# E-21_Neopixel_Blaster.net
KiCad netlist of a schematic drawn in Altium Designer
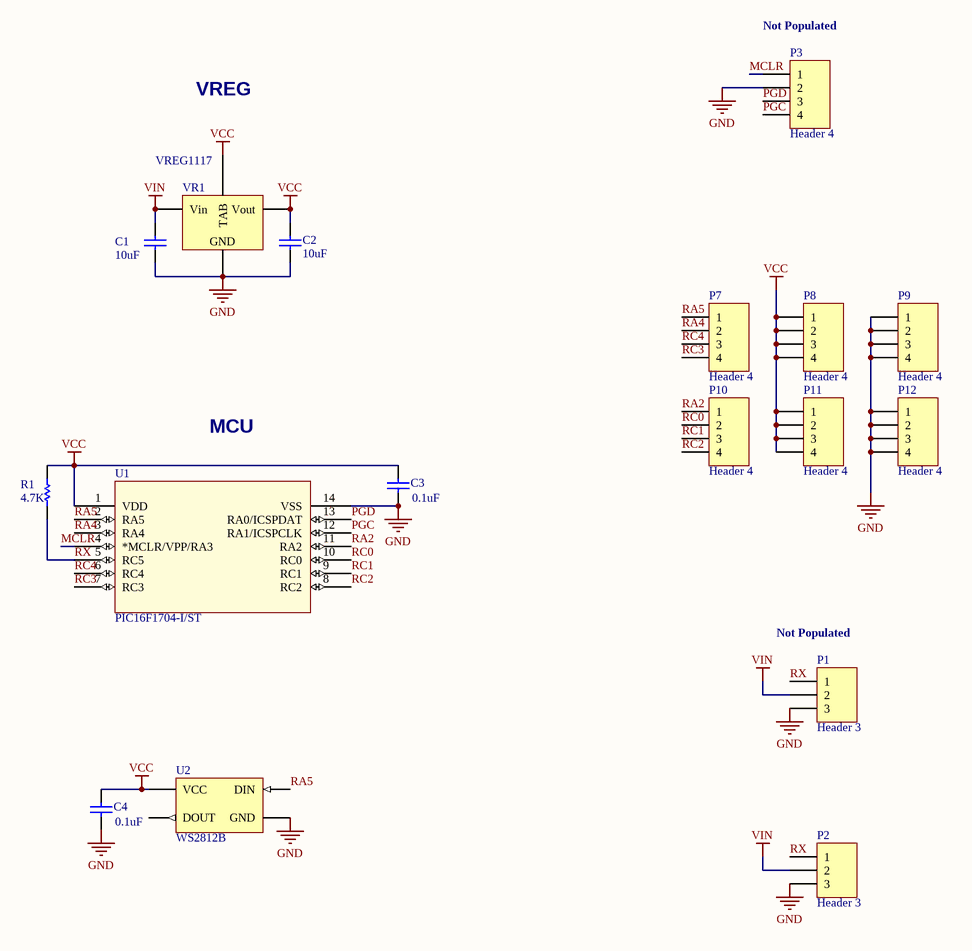
[diagram p0: E-21 Neopixel Blaster.SchDoc]

(export (version "E")
  (design (tool "Eeschema 10.0.6"))
  (components
    (comp (ref "C1")
      (value "10uF")
      (footprint "0805")
      (description "Capacitor")
      (fields (field (name "Comment") "Cap") (field (name "PUBLISHER") "Altium Limited"))
      (libsource (lib "SB_Discrete") (part "Cap"))
    )
    (comp (ref "C2")
      (value "10uF")
      (footprint "0805")
      (description "Capacitor")
      (fields (field (name "Comment") "Cap") (field (name "PUBLISHER") "Altium Limited"))
      (libsource (lib "SB_Discrete") (part "Cap"))
    )
    (comp (ref "C3")
      (value "0.1uF")
      (footprint "0805 TIGHT")
      (description "Capacitor")
      (fields (field (name "Comment") "18pF") (field (name "PUBLISHER") "Altium Limited"))
      (libsource (lib "SB_Discrete") (part "Cap"))
    )
    (comp (ref "C4")
      (value "0.1uF")
      (footprint "0805 TIGHT")
      (description "Capacitor")
      (fields (field (name "Comment") "18pF") (field (name "PUBLISHER") "Altium Limited"))
      (libsource (lib "SB_Discrete") (part "Cap"))
    )
    (comp (ref "P1")
      (value "Header 3")
      (footprint "HDR1X3")
      (description "Header, 3-Pin")
      (fields (field (name "PUBLISHER") "Altium Limited"))
      (libsource (lib "Miscellaneous Connectors") (part "Header 3"))
    )
    (comp (ref "P2")
      (value "Header 3")
      (footprint "JST-PH 3-PIN")
      (description "Header, 3-Pin")
      (fields (field (name "PUBLISHER") "Altium Limited"))
      (libsource (lib "Miscellaneous Connectors") (part "Header 3"))
    )
    (comp (ref "P3")
      (value "Header 4")
      (footprint "MINI PROG4")
      (description "Header, 4-Pin")
      (fields (field (name "PUBLISHER") "Altium Limited"))
      (libsource (lib "Miscellaneous Connectors") (part "Header 4"))
    )
    (comp (ref "P7")
      (value "Header 4")
      (footprint "HDR1X4")
      (description "Header, 4-Pin")
      (fields (field (name "PUBLISHER") "Altium Limited"))
      (libsource (lib "Miscellaneous Connectors") (part "Header 4"))
    )
    (comp (ref "P8")
      (value "Header 4")
      (footprint "HDR1X4")
      (description "Header, 4-Pin")
      (fields (field (name "PUBLISHER") "Altium Limited"))
      (libsource (lib "Miscellaneous Connectors") (part "Header 4"))
    )
    (comp (ref "P9")
      (value "Header 4")
      (footprint "HDR1X4")
      (description "Header, 4-Pin")
      (fields (field (name "PUBLISHER") "Altium Limited"))
      (libsource (lib "Miscellaneous Connectors") (part "Header 4"))
    )
    (comp (ref "P10")
      (value "Header 4")
      (footprint "HDR1X4")
      (description "Header, 4-Pin")
      (fields (field (name "PUBLISHER") "Altium Limited"))
      (libsource (lib "Miscellaneous Connectors") (part "Header 4"))
    )
    (comp (ref "P11")
      (value "Header 4")
      (footprint "HDR1X4")
      (description "Header, 4-Pin")
      (fields (field (name "PUBLISHER") "Altium Limited"))
      (libsource (lib "Miscellaneous Connectors") (part "Header 4"))
    )
    (comp (ref "P12")
      (value "Header 4")
      (footprint "HDR1X4")
      (description "Header, 4-Pin")
      (fields (field (name "PUBLISHER") "Altium Limited"))
      (libsource (lib "Miscellaneous Connectors") (part "Header 4"))
    )
    (comp (ref "R1")
      (value "4.7K")
      (footprint "0805 TIGHT")
      (description "Resistor")
      (fields (field (name "Comment") "Res1") (field (name "PUBLISHER") "Altium Limited"))
      (libsource (lib "SB_Discrete") (part "Res1"))
    )
    (comp (ref "U1")
      (value "PIC16F1704-I/ST")
      (footprint "TSSOP14")
      (libsource (lib "SB_Engineered_Components") (part "PIC16F1503"))
    )
    (comp (ref "U2")
      (value "WS2812B")
      (footprint "ws2812b")
      (libsource (lib "SB_Engineered_Components") (part "WS2812B"))
    )
    (comp (ref "VR1")
      (value "VREG1117")
      (footprint "VREG1117")
      (libsource (lib "SB_Engineered_Components") (part "VREG1117"))
    )
  )
  (nets
    (net (code "1") (name "/MCLR") (class "Default")
      (node (ref "P3") (pin "1") (pinfunction "1_1") (pintype "passive"))
      (node (ref "U1") (pin "4") (pinfunction "*MCLR/VPP/RA3_4") (pintype "bidirectional"))
    )
    (net (code "2") (name "/PGC") (class "Default")
      (node (ref "P3") (pin "4") (pinfunction "4_4") (pintype "passive"))
      (node (ref "U1") (pin "12") (pinfunction "RA1/ICSPCLK_12") (pintype "bidirectional"))
    )
    (net (code "3") (name "/PGD") (class "Default")
      (node (ref "P3") (pin "3") (pinfunction "3_3") (pintype "passive"))
      (node (ref "U1") (pin "13") (pinfunction "RA0/ICSPDAT_13") (pintype "bidirectional"))
    )
    (net (code "4") (name "/RA2") (class "Default")
      (node (ref "P10") (pin "1") (pinfunction "1_1") (pintype "passive"))
      (node (ref "U1") (pin "11") (pinfunction "RA2_11") (pintype "bidirectional"))
    )
    (net (code "5") (name "/RA4") (class "Default")
      (node (ref "P7") (pin "2") (pinfunction "2_2") (pintype "passive"))
      (node (ref "U1") (pin "3") (pinfunction "RA4_3") (pintype "bidirectional"))
    )
    (net (code "6") (name "/RA5") (class "Default")
      (node (ref "P7") (pin "1") (pinfunction "1_1") (pintype "passive"))
      (node (ref "U1") (pin "2") (pinfunction "RA5_2") (pintype "bidirectional"))
      (node (ref "U2") (pin "4") (pinfunction "DIN_4") (pintype "input"))
    )
    (net (code "7") (name "/RC0") (class "Default")
      (node (ref "P10") (pin "2") (pinfunction "2_2") (pintype "passive"))
      (node (ref "U1") (pin "10") (pinfunction "RC0_10") (pintype "bidirectional"))
    )
    (net (code "8") (name "/RC1") (class "Default")
      (node (ref "P10") (pin "3") (pinfunction "3_3") (pintype "passive"))
      (node (ref "U1") (pin "9") (pinfunction "RC1_9") (pintype "bidirectional"))
    )
    (net (code "9") (name "/RC2") (class "Default")
      (node (ref "P10") (pin "4") (pinfunction "4_4") (pintype "passive"))
      (node (ref "U1") (pin "8") (pinfunction "RC2_8") (pintype "bidirectional"))
    )
    (net (code "10") (name "/RC3") (class "Default")
      (node (ref "P7") (pin "4") (pinfunction "4_4") (pintype "passive"))
      (node (ref "U1") (pin "7") (pinfunction "RC3_7") (pintype "bidirectional"))
    )
    (net (code "11") (name "/RC4") (class "Default")
      (node (ref "P7") (pin "3") (pinfunction "3_3") (pintype "passive"))
      (node (ref "U1") (pin "6") (pinfunction "RC4_6") (pintype "bidirectional"))
    )
    (net (code "12") (name "/RX") (class "Default")
      (node (ref "P1") (pin "1") (pinfunction "1_1") (pintype "passive"))
      (node (ref "P2") (pin "1") (pinfunction "1_1") (pintype "passive"))
      (node (ref "R1") (pin "1") (pinfunction "1_1") (pintype "passive"))
      (node (ref "U1") (pin "5") (pinfunction "RC5_5") (pintype "bidirectional"))
    )
    (net (code "13") (name "GND") (class "Default")
      (node (ref "C1") (pin "2") (pinfunction "2_2") (pintype "passive"))
      (node (ref "C2") (pin "2") (pinfunction "2_2") (pintype "passive"))
      (node (ref "C3") (pin "1") (pinfunction "1_1") (pintype "passive"))
      (node (ref "C4") (pin "1") (pinfunction "1_1") (pintype "passive"))
      (node (ref "P1") (pin "3") (pinfunction "3_3") (pintype "passive"))
      (node (ref "P12") (pin "1") (pinfunction "1_1") (pintype "passive"))
      (node (ref "P12") (pin "2") (pinfunction "2_2") (pintype "passive"))
      (node (ref "P12") (pin "3") (pinfunction "3_3") (pintype "passive"))
      (node (ref "P12") (pin "4") (pinfunction "4_4") (pintype "passive"))
      (node (ref "P2") (pin "3") (pinfunction "3_3") (pintype "passive"))
      (node (ref "P3") (pin "2") (pinfunction "2_2") (pintype "passive"))
      (node (ref "P9") (pin "1") (pinfunction "1_1") (pintype "passive"))
      (node (ref "P9") (pin "2") (pinfunction "2_2") (pintype "passive"))
      (node (ref "P9") (pin "3") (pinfunction "3_3") (pintype "passive"))
      (node (ref "P9") (pin "4") (pinfunction "4_4") (pintype "passive"))
      (node (ref "U1") (pin "14") (pinfunction "VSS_14") (pintype "power_in"))
      (node (ref "U2") (pin "3") (pinfunction "GND_3") (pintype "power_in"))
      (node (ref "VR1") (pin "1") (pinfunction "GND_1") (pintype "passive"))
    )
    (net (code "14") (name "VCC") (class "Default")
      (node (ref "C2") (pin "1") (pinfunction "1_1") (pintype "passive"))
      (node (ref "C3") (pin "2") (pinfunction "2_2") (pintype "passive"))
      (node (ref "C4") (pin "2") (pinfunction "2_2") (pintype "passive"))
      (node (ref "P11") (pin "1") (pinfunction "1_1") (pintype "passive"))
      (node (ref "P11") (pin "2") (pinfunction "2_2") (pintype "passive"))
      (node (ref "P11") (pin "3") (pinfunction "3_3") (pintype "passive"))
      (node (ref "P11") (pin "4") (pinfunction "4_4") (pintype "passive"))
      (node (ref "P8") (pin "1") (pinfunction "1_1") (pintype "passive"))
      (node (ref "P8") (pin "2") (pinfunction "2_2") (pintype "passive"))
      (node (ref "P8") (pin "3") (pinfunction "3_3") (pintype "passive"))
      (node (ref "P8") (pin "4") (pinfunction "4_4") (pintype "passive"))
      (node (ref "R1") (pin "2") (pinfunction "2_2") (pintype "passive"))
      (node (ref "U1") (pin "1") (pinfunction "VDD_1") (pintype "power_in"))
      (node (ref "U2") (pin "1") (pinfunction "VCC_1") (pintype "power_in"))
      (node (ref "VR1") (pin "2") (pinfunction "Vout_2") (pintype "passive"))
    )
    (net (code "15") (name "VIN") (class "Default")
      (node (ref "C1") (pin "1") (pinfunction "1_1") (pintype "passive"))
      (node (ref "P1") (pin "2") (pinfunction "2_2") (pintype "passive"))
      (node (ref "P2") (pin "2") (pinfunction "2_2") (pintype "passive"))
      (node (ref "VR1") (pin "3") (pinfunction "Vin_3") (pintype "passive"))
    )
    (net (code "16") (name "unconnected-(U2-DOUT-Pad2)") (class "Default")
      (node (ref "U2") (pin "2") (pinfunction "DOUT_2") (pintype "output"))
    )
  )
)
